# circuit.net
KiCad netlist of a schematic drawn in Altium Designer
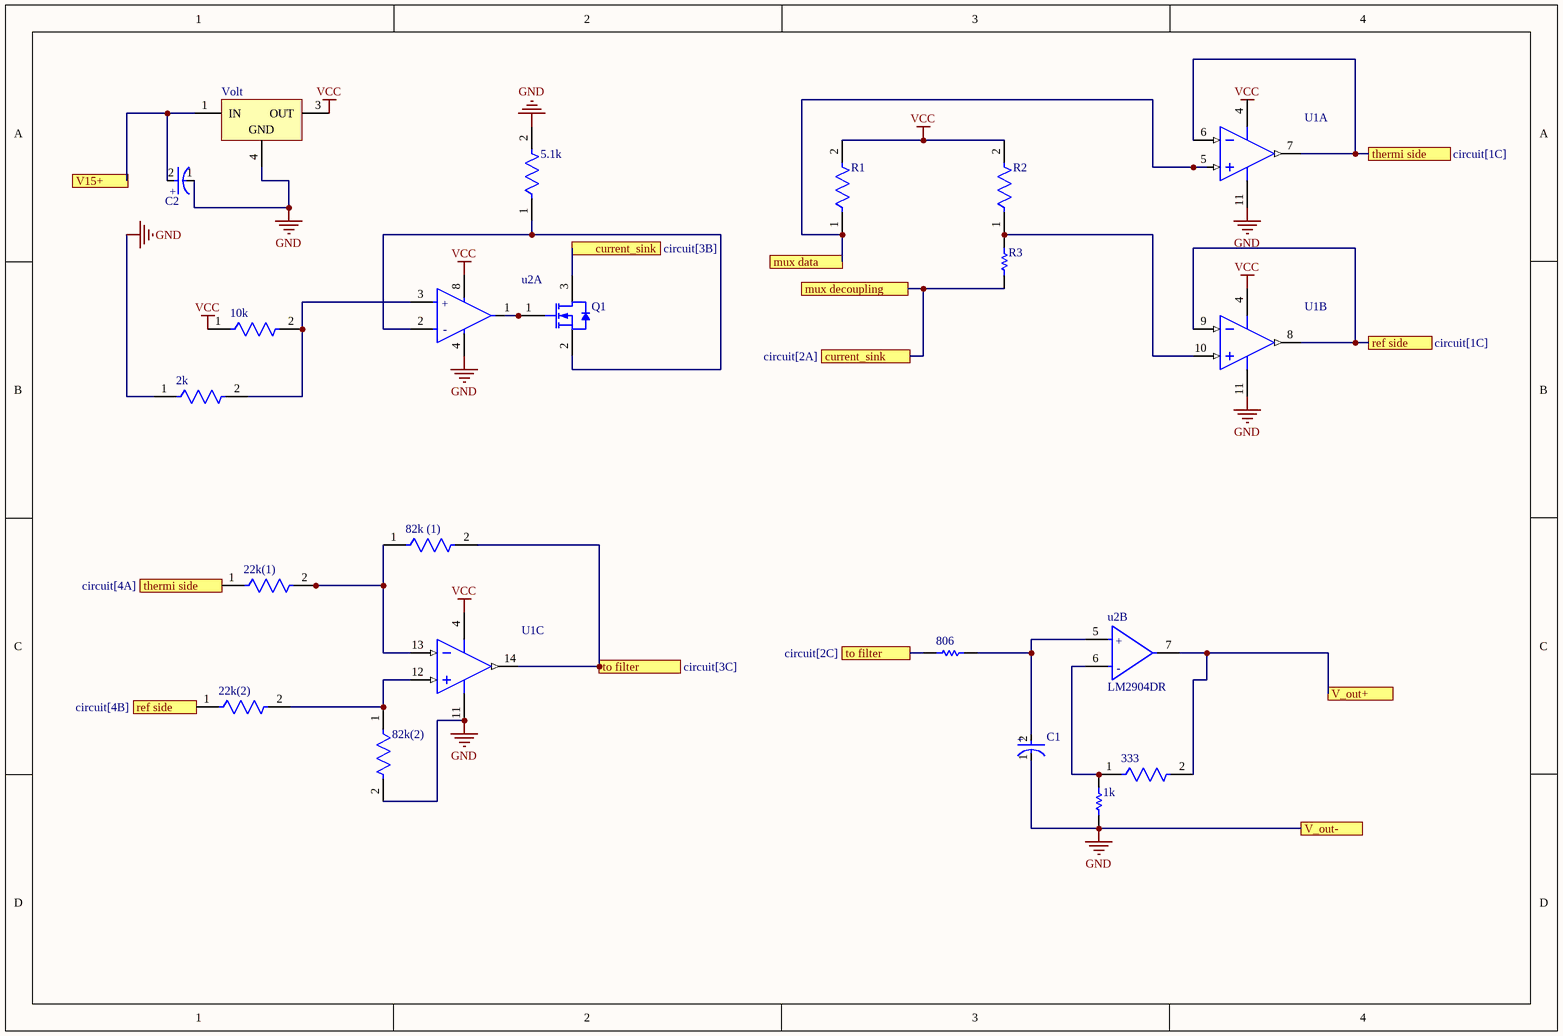
[diagram p0: circuit.SchDoc]

(export (version "E")
  (design (tool "Eeschema 10.0.6"))
  (components
    (comp (ref "1k")
      (value "CRCW12101K00FKEAHP")
      (footprint "RESC3225X60X45NL20T20")
      (fields (field (name "MANUFACTURER") "Vishay Dale"))
      (libsource (lib "Altium Content Vault") (part "RES"))
    )
    (comp (ref "2k")
      (value "CRCW12062K00FKEA")
      (footprint "FP-CRCW1206-e3-IPC_A")
      (description "RES Thick Film, 2kΩ, 1%, 0.25W, 100ppm/°C, 1206")
      (fields (field (name "TOLERANCE") "1%"))
      (libsource (lib "Altium Content Vault") (part "1029c3af85768c4190bb7ad29bc67b5"))
    )
    (comp (ref "5.1k")
      (value "CRCW12065K10FKEA")
      (footprint "FP-CRCW1206-e3-IPC_C")
      (description "RES Thick Film, 5.1kΩ, 1%, 0.25W, 100ppm/°C, 1206")
      (fields (field (name "TOLERANCE") "1%"))
      (libsource (lib "Altium Content Vault") (part "1029c3af85768c4190bb7ad29bc67b5"))
    )
    (comp (ref "10k")
      (value "CRCW120610K0FKEA")
      (footprint "FP-CRCW1206-e3-IPC_C")
      (description "RES Thick Film, 10kΩ, 1%, 0.25W, 100ppm/°C, 1206")
      (fields (field (name "TOLERANCE") "1%"))
      (libsource (lib "Altium Content Vault") (part "1029c3af85768c4190bb7ad29bc67b5"))
    )
    (comp (ref "22k(1)")
      (value "CRCW120622K0FKEA")
      (footprint "FP-CRCW1206-e3-IPC_A")
      (description "RES Thick Film, 22kΩ, 1%, 0.25W, 100ppm/°C, 1206")
      (fields (field (name "TOLERANCE") "1%"))
      (libsource (lib "Altium Content Vault") (part "1029c3af85768c4190bb7ad29bc67b5"))
    )
    (comp (ref "22k(2)")
      (value "CRCW120622K0FKEA")
      (footprint "FP-CRCW1206-e3-IPC_A")
      (description "RES Thick Film, 22kΩ, 1%, 0.25W, 100ppm/°C, 1206")
      (fields (field (name "TOLERANCE") "1%"))
      (libsource (lib "Altium Content Vault") (part "1029c3af85768c4190bb7ad29bc67b5"))
    )
    (comp (ref "82k (1)")
      (value "CRCW120682K0FKEA")
      (footprint "FP-CRCW1206-e3-IPC_B")
      (description "RES Thick Film, 82kΩ, 1%, 0.25W, 100ppm/°C, 1206")
      (fields (field (name "TOLERANCE") "1%"))
      (libsource (lib "Altium Content Vault") (part "1029c3af85768c4190bb7ad29bc67b5"))
    )
    (comp (ref "82k(2)")
      (value "CRCW120682K0FKEA")
      (footprint "FP-CRCW1206-e3-IPC_B")
      (description "RES Thick Film, 82kΩ, 1%, 0.25W, 100ppm/°C, 1206")
      (fields (field (name "TOLERANCE") "1%"))
      (libsource (lib "Altium Content Vault") (part "1029c3af85768c4190bb7ad29bc67b5"))
    )
    (comp (ref "333")
      (value "CRCW0603330RFKEAHP")
      (footprint "FP-CRCW0603-HPe3-IPC_C")
      (description "RES Thick Film, 330Ω, 1%, 0.33W, 100ppm/°C, 0603")
      (fields (field (name "TOLERANCE") "1%"))
      (libsource (lib "Altium Content Vault") (part "1029c3af85768c4190bb7ad29bc67b5"))
    )
    (comp (ref "806")
      (value "RC1206FR-07806RL")
      (footprint "RESC3116X65X40NL10T20")
      (fields (field (name "MANUFACTURER") "Yageo"))
      (libsource (lib "Altium Content Vault") (part "RES"))
    )
    (comp (ref "C1")
      (value "TAJA106K016RNJ")
      (footprint "FP-TAJA-MFG")
      (description "10uF 16V  ±10% 3Ω 1206  SMD Tantalum Capacitor")
      (fields (field (name "VOLTAGE") "16V") (field (name "TOLERANCE") "10%"))
      (libsource (lib "Altium Content Vault") (part "203bc49f2ac43e59fd269a8c329ed05"))
    )
    (comp (ref "C2")
      (value "TAJA106K016RNJ")
      (footprint "FP-TAJA-MFG")
      (description "10uF 16V  ±10% 3Ω 1206  SMD Tantalum Capacitor")
      (fields (field (name "VOLTAGE") "16V") (field (name "TOLERANCE") "10%"))
      (libsource (lib "Altium Content Vault") (part "203bc49f2ac43e59fd269a8c329ed05"))
    )
    (comp (ref "Q1")
      (value "MGSF1N02LT1G")
      (footprint "ONSC-SOT-23-3-318-08_V")
      (description "Power MOSFET, 750 mA, 20 V, N-Channel, 3-Pin SOT-23, Pb-Free, Tape and Reel")
      (fields (field (name "MANUFACTURER") "On Semiconductor"))
      (libsource (lib "Altium Content Vault") (part "ONSC-NMOS-G1S2D3-3"))
    )
    (comp (ref "R1")
      (value "CRCW080540K0FKEA")
      (footprint "FP-CRCW0805-e3-MFG")
      (description "RES Thick Film, 40kΩ, 1%, 0.125W, 100ppm/°C, 0805")
      (fields (field (name "TOLERANCE") "1%"))
      (libsource (lib "Altium Content Vault") (part "1029c3af85768c4190bb7ad29bc67b5"))
    )
    (comp (ref "R2")
      (value "CRCW080540K0FKEA")
      (footprint "FP-CRCW0805-e3-MFG")
      (description "RES Thick Film, 40kΩ, 1%, 0.125W, 100ppm/°C, 0805")
      (fields (field (name "TOLERANCE") "1%"))
      (libsource (lib "Altium Content Vault") (part "1029c3af85768c4190bb7ad29bc67b5"))
    )
    (comp (ref "R3")
      (value "CRCW120615K0FKEA")
      (footprint "RESC3216X60X45LL10T20")
      (fields (field (name "MANUFACTURER") "Vishay Dale"))
      (libsource (lib "Altium Content Vault") (part "RES"))
    )
    (comp (ref "U1")
      (value "LMH6683MA/NOPB")
      (footprint "D0014A_M")
      (description "190MHz Single Supply, Dual and Triple Operational Amplifiers, 14-pin Narrow SOIC, Pb-Free")
      (fields (field (name "MANUFACTURER") "Texas Instruments"))
      (libsource (lib "Altium Content Vault") (part "AMP-OPA-LMH6683-14"))
    )
    (comp (ref "u2")
      (value "LM2904DR")
      (footprint "FP-D0008A-MFG")
      (description "IC OPAMP GP 2 CIRCUIT 8SOIC")
      (fields
        (field (name "OCTOPART") "https://octopart.com/lm2904dr-texas+instruments-409181")
        (field (name "MANUFACTURER") "Texas Instruments")
      )
      (libsource (lib "Altium Content Vault") (part "4badc4d003422c0e8025c31f261cee9"))
    )
    (comp (ref "Volt")
      (value "L7812CD2T-TR")
      (footprint "TO-263_M")
      (description "Positive Voltage Regulator, 3-Pin D2PAK, Tape and Reel")
      (libsource (lib "Altium Content Vault") (part "PM-REG-L4940-SOT3"))
    )
  )
  (nets
    (net (code "2") (name "/V_out+") (class "Default")
      (node (ref "333") (pin "2") (pinfunction "2_2") (pintype "passive"))
      (node (ref "u2") (pin "7") (pinfunction "OUT2_7") (pintype "passive"))
    )
    (net (code "3") (name "/current_sink") (class "Default")
      (node (ref "Q1") (pin "3") (pinfunction "D_3") (pintype "passive"))
      (node (ref "R3") (pin "1") (pinfunction "1_1") (pintype "passive"))
    )
    (net (code "4") (name "/mux data") (class "Default")
      (node (ref "R1") (pin "1") (pinfunction "1_1") (pintype "passive"))
      (node (ref "U1") (pin "5") (pinfunction "IN1+_5") (pintype "input"))
    )
    (net (code "5") (name "/ref side") (class "Default")
      (node (ref "22k(2)") (pin "1") (pinfunction "1_1") (pintype "passive"))
      (node (ref "U1") (pin "8") (pinfunction "OUT2_8") (pintype "output"))
      (node (ref "U1") (pin "9") (pinfunction "IN2-_9") (pintype "input"))
    )
    (net (code "6") (name "/thermi side") (class "Default")
      (node (ref "22k(1)") (pin "1") (pinfunction "1_1") (pintype "passive"))
      (node (ref "U1") (pin "6") (pinfunction "IN1-_6") (pintype "input"))
      (node (ref "U1") (pin "7") (pinfunction "OUT1_7") (pintype "output"))
    )
    (net (code "7") (name "/to filter") (class "Default")
      (node (ref "806") (pin "1") (pinfunction "1_1") (pintype "passive"))
      (node (ref "82k (1)") (pin "2") (pinfunction "2_2") (pintype "passive"))
      (node (ref "U1") (pin "14") (pinfunction "OUT3_14") (pintype "output"))
    )
    (net (code "8") (name "GND") (class "Default")
      (node (ref "1k") (pin "1") (pinfunction "1_1") (pintype "passive"))
      (node (ref "2k") (pin "1") (pinfunction "1_1") (pintype "passive"))
      (node (ref "5.1k") (pin "2") (pinfunction "2_2") (pintype "passive"))
      (node (ref "82k(2)") (pin "2") (pinfunction "2_2") (pintype "passive"))
      (node (ref "C1") (pin "1") (pinfunction "C_1") (pintype "passive"))
      (node (ref "C2") (pin "1") (pinfunction "C_1") (pintype "passive"))
      (node (ref "U1") (pin "11") (pinfunction "V-_11") (pintype "power_in"))
      (node (ref "Volt") (pin "4") (pinfunction "GND_4") (pintype "power_in"))
      (node (ref "u2") (pin "4") (pinfunction "V-_4") (pintype "power_in"))
    )
    (net (code "9") (name "Net-(C1-A)") (class "Default")
      (node (ref "806") (pin "2") (pinfunction "2_2") (pintype "passive"))
      (node (ref "C1") (pin "2") (pinfunction "A_2") (pintype "passive"))
      (node (ref "u2") (pin "5") (pinfunction "IN2+_5") (pintype "tri_state"))
    )
    (net (code "10") (name "Net-(C2-A)") (class "Default")
      (node (ref "C2") (pin "2") (pinfunction "A_2") (pintype "passive"))
      (node (ref "Volt") (pin "1") (pinfunction "IN_1") (pintype "power_in"))
    )
    (net (code "11") (name "Net-(Q1-G)") (class "Default")
      (node (ref "Q1") (pin "1") (pinfunction "G_1") (pintype "passive"))
      (node (ref "u2") (pin "1") (pinfunction "OUT1_1") (pintype "passive"))
    )
    (net (code "12") (name "Net-(Q1-S)") (class "Default")
      (node (ref "5.1k") (pin "1") (pinfunction "1_1") (pintype "passive"))
      (node (ref "Q1") (pin "2") (pinfunction "S_2") (pintype "passive"))
      (node (ref "u2") (pin "2") (pinfunction "IN1-_2") (pintype "tri_state"))
    )
    (net (code "13") (name "Net-(U1B-IN2+)") (class "Default")
      (node (ref "R2") (pin "1") (pinfunction "1_1") (pintype "passive"))
      (node (ref "R3") (pin "2") (pinfunction "2_2") (pintype "passive"))
      (node (ref "U1") (pin "10") (pinfunction "IN2+_10") (pintype "input"))
    )
    (net (code "14") (name "Net-(U1C-IN3+)") (class "Default")
      (node (ref "22k(2)") (pin "2") (pinfunction "2_2") (pintype "passive"))
      (node (ref "82k(2)") (pin "1") (pinfunction "1_1") (pintype "passive"))
      (node (ref "U1") (pin "12") (pinfunction "IN3+_12") (pintype "input"))
    )
    (net (code "15") (name "Net-(U1C-IN3-)") (class "Default")
      (node (ref "22k(1)") (pin "2") (pinfunction "2_2") (pintype "passive"))
      (node (ref "82k (1)") (pin "1") (pinfunction "1_1") (pintype "passive"))
      (node (ref "U1") (pin "13") (pinfunction "IN3-_13") (pintype "input"))
    )
    (net (code "16") (name "Net-(u2A-IN1+)") (class "Default")
      (node (ref "10k") (pin "2") (pinfunction "2_2") (pintype "passive"))
      (node (ref "2k") (pin "2") (pinfunction "2_2") (pintype "passive"))
      (node (ref "u2") (pin "3") (pinfunction "IN1+_3") (pintype "tri_state"))
    )
    (net (code "17") (name "Net-(u2B-IN2-)") (class "Default")
      (node (ref "1k") (pin "2") (pinfunction "2_2") (pintype "passive"))
      (node (ref "333") (pin "1") (pinfunction "1_1") (pintype "passive"))
      (node (ref "u2") (pin "6") (pinfunction "IN2-_6") (pintype "tri_state"))
    )
    (net (code "18") (name "VCC") (class "Default")
      (node (ref "10k") (pin "1") (pinfunction "1_1") (pintype "passive"))
      (node (ref "R1") (pin "2") (pinfunction "2_2") (pintype "passive"))
      (node (ref "R2") (pin "2") (pinfunction "2_2") (pintype "passive"))
      (node (ref "U1") (pin "4") (pinfunction "V+_4") (pintype "power_in"))
      (node (ref "Volt") (pin "3") (pinfunction "OUT_3") (pintype "power_in"))
      (node (ref "u2") (pin "8") (pinfunction "V+_8") (pintype "power_in"))
    )
    (net (code "19") (name "unconnected-(U1A-V+-Pad4)") (class "Default")
      (node (ref "U1") (pin "4") (pinfunction "V+_4") (pintype "power_in"))
    )
  )
)
